# Domino_I2S_No_Teardrop.net
KiCad netlist of a schematic drawn in EAGLE
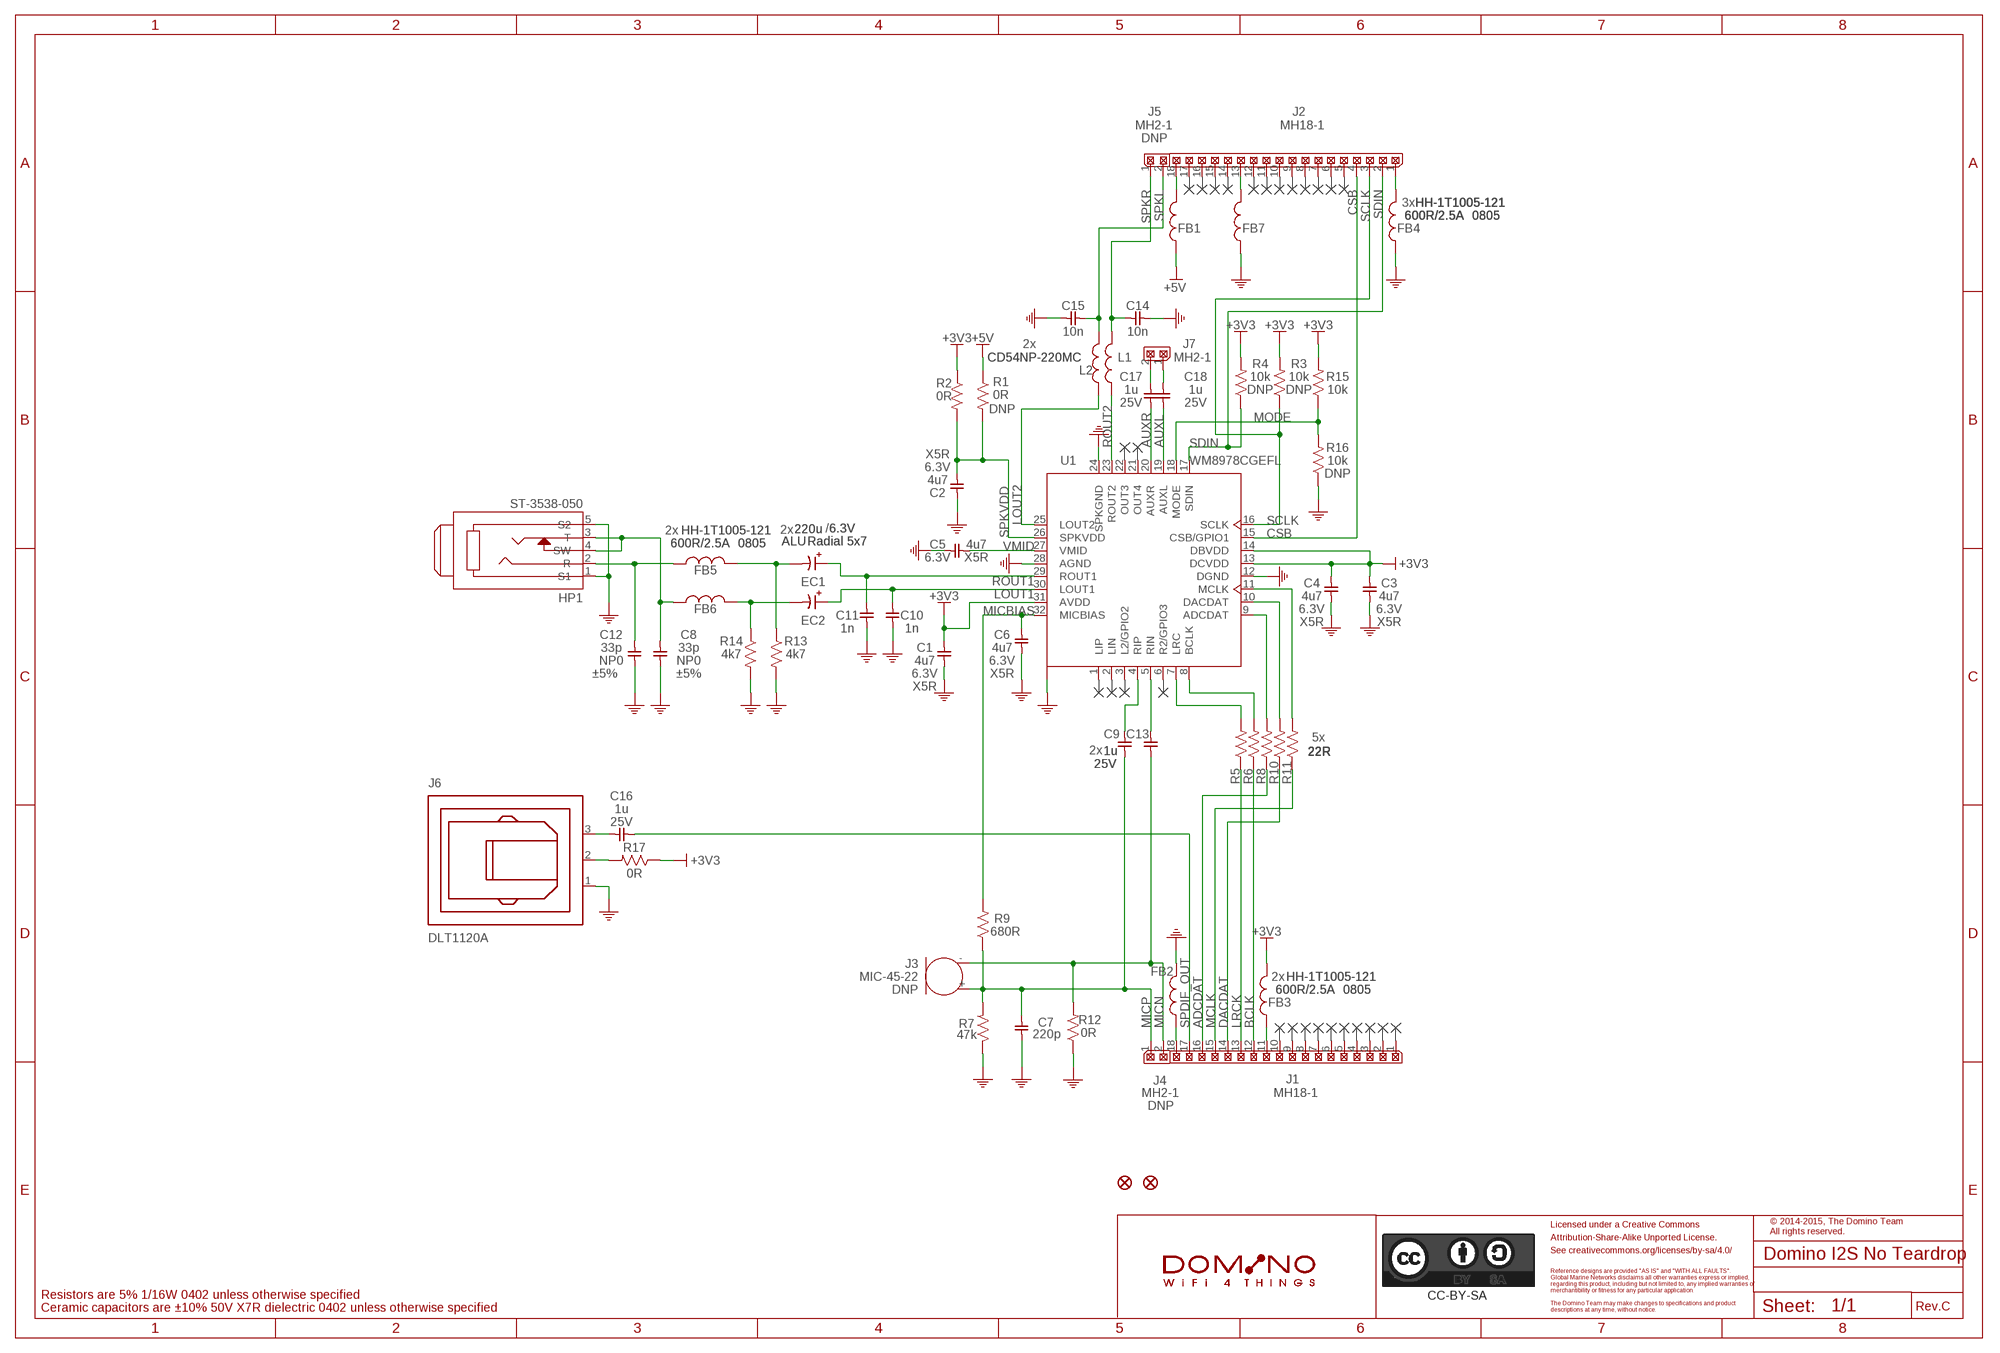
[diagram p0: schematic, sheet 1]

(export (version "E")
  (design (tool "Eeschema 10.0.6"))
  (components
    (comp (ref "C1")
      (value "4u7")
      (footprint "eagle-import:C0402")
      (fields
        (field (name "PARTNO") "C0402_4u7_X5R_10%_CER_6V3")
        (field (name "TC") "X5R")
        (field (name "VOLT") "6.3V")
      )
      (libsource (lib "eagle-import") (part "CAP_0402"))
    )
    (comp (ref "C2")
      (value "4u7")
      (footprint "eagle-import:C0402")
      (fields
        (field (name "PARTNO") "C0402_4u7_X5R_10%_CER_6V3")
        (field (name "TC") "X5R")
        (field (name "VOLT") "6.3V")
      )
      (libsource (lib "eagle-import") (part "CAP_0402"))
    )
    (comp (ref "C3")
      (value "4u7")
      (footprint "eagle-import:C0402")
      (fields
        (field (name "PARTNO") "C0402_4u7_X5R_10%_CER_6V3")
        (field (name "TC") "X5R")
        (field (name "VOLT") "6.3V")
      )
      (libsource (lib "eagle-import") (part "CAP_0402"))
    )
    (comp (ref "C4")
      (value "4u7")
      (footprint "eagle-import:C0402")
      (fields
        (field (name "PARTNO") "C0402_4u7_X5R_10%_CER_6V3")
        (field (name "TC") "X5R")
        (field (name "VOLT") "6.3V")
      )
      (libsource (lib "eagle-import") (part "CAP_0402"))
    )
    (comp (ref "C5")
      (value "4u7")
      (footprint "eagle-import:C0402")
      (fields
        (field (name "PARTNO") "C0402_4u7_X5R_10%_CER_6V3")
        (field (name "TC") "X5R")
        (field (name "VOLT") "6.3V")
      )
      (libsource (lib "eagle-import") (part "CAP_0402"))
    )
    (comp (ref "C6")
      (value "4u7")
      (footprint "eagle-import:C0402")
      (fields
        (field (name "PARTNO") "C0402_4u7_X5R_10%_CER_6V3")
        (field (name "TC") "X5R")
        (field (name "VOLT") "6.3V")
      )
      (libsource (lib "eagle-import") (part "CAP_0402"))
    )
    (comp (ref "C7")
      (value "220p")
      (footprint "eagle-import:C0402")
      (fields (field (name "PARTNO") "C0402_220p_X7R_10%_CER_50V"))
      (libsource (lib "eagle-import") (part "CAP_0402"))
    )
    (comp (ref "C8")
      (value "33p")
      (footprint "eagle-import:C0402")
      (fields
        (field (name "PARTNO") "C0402_33p_NP0_5%_CER_50V")
        (field (name "TC") "NP0")
        (field (name "TOL") "±5%")
      )
      (libsource (lib "eagle-import") (part "CAP_0402"))
    )
    (comp (ref "C9")
      (value "1u")
      (footprint "eagle-import:C0402")
      (fields (field (name "PARTNO") "C0402_1u_X7R_10%_CER_25V") (field (name "VOLT") "25V"))
      (libsource (lib "eagle-import") (part "CAP_0402"))
    )
    (comp (ref "C10")
      (value "1n")
      (footprint "eagle-import:C0402")
      (fields (field (name "PARTNO") "C0402_1n_X7R_10%_CER_50V"))
      (libsource (lib "eagle-import") (part "CAP_0402"))
    )
    (comp (ref "C11")
      (value "1n")
      (footprint "eagle-import:C0402")
      (fields (field (name "PARTNO") "C0402_1n_X7R_10%_CER_50V"))
      (libsource (lib "eagle-import") (part "CAP_0402"))
    )
    (comp (ref "C12")
      (value "33p")
      (footprint "eagle-import:C0402")
      (fields
        (field (name "PARTNO") "C0402_33p_NP0_5%_CER_50V")
        (field (name "TC") "NP0")
        (field (name "TOL") "±5%")
      )
      (libsource (lib "eagle-import") (part "CAP_0402"))
    )
    (comp (ref "C13")
      (value "1u")
      (footprint "eagle-import:C0402")
      (fields (field (name "PARTNO") "C0402_1u_X7R_10%_CER_25V") (field (name "VOLT") "25V"))
      (libsource (lib "eagle-import") (part "CAP_0402"))
    )
    (comp (ref "C14")
      (value "10n")
      (footprint "eagle-import:C0402")
      (fields (field (name "PARTNO") "C0402_10n_X7R_10%_CER_50V"))
      (libsource (lib "eagle-import") (part "CAP_0402"))
    )
    (comp (ref "C15")
      (value "10n")
      (footprint "eagle-import:C0402")
      (fields (field (name "PARTNO") "C0402_10n_X7R_10%_CER_50V"))
      (libsource (lib "eagle-import") (part "CAP_0402"))
    )
    (comp (ref "C16")
      (value "1u")
      (footprint "eagle-import:C0402")
      (fields (field (name "PARTNO") "C0402_1u_X7R_10%_CER_25V") (field (name "VOLT") "25V"))
      (libsource (lib "eagle-import") (part "CAP_0402"))
    )
    (comp (ref "C17")
      (value "1u")
      (footprint "eagle-import:C0402")
      (fields (field (name "PARTNO") "C0402_1u_X7R_10%_CER_25V") (field (name "VOLT") "25V"))
      (libsource (lib "eagle-import") (part "CAP_0402"))
    )
    (comp (ref "C18")
      (value "1u")
      (footprint "eagle-import:C0402")
      (fields (field (name "PARTNO") "C0402_1u_X7R_10%_CER_25V") (field (name "VOLT") "25V"))
      (libsource (lib "eagle-import") (part "CAP_0402"))
    )
    (comp (ref "CC-BY-SA101")
      (value "CC-BY-SA_LOGO")
      (footprint "eagle-import:CC-BY-SA_LOGO")
      (libsource (lib "eagle-import") (part "CC-BY-SA_LOGO"))
    )
    (comp (ref "EC1")
      (value "220u")
      (footprint "eagle-import:E2-5")
      (fields
        (field (name "SIZE") "Radial 5x7")
        (field (name "TYPE") "ALU")
        (field (name "PARTNO") "C2-5x7_220u_ALU_20%_RAD_6V3")
        (field (name "VOLT") "6.3V")
      )
      (libsource (lib "eagle-import") (part "CPOL_?E2-5X7"))
    )
    (comp (ref "EC2")
      (value "220u")
      (footprint "eagle-import:E2-5")
      (fields
        (field (name "SIZE") "Radial 5x7")
        (field (name "TYPE") "ALU")
        (field (name "PARTNO") "C2-5x7_220u_ALU_20%_RAD_6V3")
        (field (name "VOLT") "6.3V")
      )
      (libsource (lib "eagle-import") (part "CPOL_?E2-5X7"))
    )
    (comp (ref "F1")
      (value "FIDUCIAL")
      (footprint "eagle-import:FIDUCIAL")
      (libsource (lib "eagle-import") (part "FIDUCIAL"))
    )
    (comp (ref "F2")
      (value "FIDUCIAL")
      (footprint "eagle-import:FIDUCIAL")
      (libsource (lib "eagle-import") (part "FIDUCIAL"))
    )
    (comp (ref "FB1")
      (value "HH-1T1005-121")
      (footprint "eagle-import:FB0805")
      (fields
        (field (name "SIZE") "0805")
        (field (name "OPT") "600R/2.5A")
        (field (name "PARTNO") "HH-1T2012-601")
      )
      (libsource (lib "eagle-import") (part "FB_0805"))
    )
    (comp (ref "FB2")
      (value "HH-1T1005-121")
      (footprint "eagle-import:FB0805")
      (fields
        (field (name "SIZE") "0805")
        (field (name "OPT") "600R/2.5A")
        (field (name "PARTNO") "HH-1T2012-601")
      )
      (libsource (lib "eagle-import") (part "FB_0805"))
    )
    (comp (ref "FB3")
      (value "HH-1T1005-121")
      (footprint "eagle-import:FB0805")
      (fields
        (field (name "SIZE") "0805")
        (field (name "OPT") "600R/2.5A")
        (field (name "PARTNO") "HH-1T2012-601")
      )
      (libsource (lib "eagle-import") (part "FB_0805"))
    )
    (comp (ref "FB4")
      (value "HH-1T1005-121")
      (footprint "eagle-import:FB0805")
      (fields
        (field (name "SIZE") "0805")
        (field (name "OPT") "600R/2.5A")
        (field (name "PARTNO") "HH-1T2012-601")
      )
      (libsource (lib "eagle-import") (part "FB_0805"))
    )
    (comp (ref "FB5")
      (value "HH-1T1005-121")
      (footprint "eagle-import:FB0805")
      (fields
        (field (name "SIZE") "0805")
        (field (name "OPT") "600R/2.5A")
        (field (name "PARTNO") "HH-1T2012-601")
      )
      (libsource (lib "eagle-import") (part "FB_0805"))
    )
    (comp (ref "FB6")
      (value "HH-1T1005-121")
      (footprint "eagle-import:FB0805")
      (fields
        (field (name "SIZE") "0805")
        (field (name "OPT") "600R/2.5A")
        (field (name "PARTNO") "HH-1T2012-601")
      )
      (libsource (lib "eagle-import") (part "FB_0805"))
    )
    (comp (ref "FB7")
      (value "HH-1T1005-121")
      (footprint "eagle-import:FB0805")
      (fields
        (field (name "SIZE") "0805")
        (field (name "OPT") "600R/2.5A")
        (field (name "PARTNO") "HH-1T2012-601")
      )
      (libsource (lib "eagle-import") (part "FB_0805"))
    )
    (comp (ref "HP1")
      (value "ST-3538-050")
      (footprint "eagle-import:ST-3538-050")
      (libsource (lib "eagle-import") (part "ST-3538-050"))
    )
    (comp (ref "J1")
      (value "MH18-1")
      (footprint "eagle-import:MH18-1-0.1")
      (fields (field (name "PARTNO") "MH18-1-0.1"))
      (libsource (lib "eagle-import") (part "MH18-1"))
    )
    (comp (ref "J2")
      (value "MH18-1")
      (footprint "eagle-import:MH18-1-0.1")
      (fields (field (name "PARTNO") "MH18-1-0.1"))
      (libsource (lib "eagle-import") (part "MH18-1"))
    )
    (comp (ref "J3")
      (value "MIC-45-22")
      (footprint "eagle-import:MIC-45-22")
      (libsource (lib "eagle-import") (part "MIC-45-22"))
    )
    (comp (ref "J4")
      (value "MH2-1")
      (footprint "eagle-import:MH2-1-0.1")
      (fields (field (name "PARTNO") "MH2-1-0.1"))
      (libsource (lib "eagle-import") (part "MH2-1"))
    )
    (comp (ref "J5")
      (value "MH2-1")
      (footprint "eagle-import:MH2-1-0.1")
      (fields (field (name "PARTNO") "MH2-1-0.1"))
      (libsource (lib "eagle-import") (part "MH2-1"))
    )
    (comp (ref "J6")
      (value "DLT1120A")
      (footprint "eagle-import:DLT1120A")
      (libsource (lib "eagle-import") (part "DLT1120A"))
    )
    (comp (ref "J7")
      (value "MH2-1")
      (footprint "eagle-import:MH2-1-0.1")
      (fields (field (name "PARTNO") "MH2-1-0.1"))
      (libsource (lib "eagle-import") (part "MH2-1"))
    )
    (comp (ref "L1")
      (value "CD54NP-220MC")
      (footprint "eagle-import:CD54")
      (libsource (lib "eagle-import") (part "CD54NP-MC220"))
    )
    (comp (ref "L2")
      (value "CD54NP-220MC")
      (footprint "eagle-import:CD54")
      (libsource (lib "eagle-import") (part "CD54NP-MC220"))
    )
    (comp (ref "R1")
      (value "0R")
      (footprint "eagle-import:R0402")
      (fields (field (name "PARTNO") "R0402_0R_5%_62.5mW"))
      (libsource (lib "eagle-import") (part "RES_0402"))
    )
    (comp (ref "R2")
      (value "0R")
      (footprint "eagle-import:R0402")
      (fields (field (name "PARTNO") "R0402_0R_5%_62.5mW"))
      (libsource (lib "eagle-import") (part "RES_0402"))
    )
    (comp (ref "R3")
      (value "10k")
      (footprint "eagle-import:R0402")
      (fields (field (name "PARTNO") "R0402_10k_5%_62.5mW"))
      (libsource (lib "eagle-import") (part "RES_0402"))
    )
    (comp (ref "R4")
      (value "10k")
      (footprint "eagle-import:R0402")
      (fields (field (name "PARTNO") "R0402_10k_5%_62.5mW"))
      (libsource (lib "eagle-import") (part "RES_0402"))
    )
    (comp (ref "R5")
      (value "22R")
      (footprint "eagle-import:R0402")
      (fields (field (name "PARTNO") "R0402_22R_5%_62.5mW"))
      (libsource (lib "eagle-import") (part "RES_0402"))
    )
    (comp (ref "R6")
      (value "22R")
      (footprint "eagle-import:R0402")
      (fields (field (name "PARTNO") "R0402_22R_5%_62.5mW"))
      (libsource (lib "eagle-import") (part "RES_0402"))
    )
    (comp (ref "R7")
      (value "47k")
      (footprint "eagle-import:R0402")
      (fields (field (name "PARTNO") "R0402_47k_5%_62.5mW"))
      (libsource (lib "eagle-import") (part "RES_0402"))
    )
    (comp (ref "R8")
      (value "22R")
      (footprint "eagle-import:R0402")
      (fields (field (name "PARTNO") "R0402_22R_5%_62.5mW"))
      (libsource (lib "eagle-import") (part "RES_0402"))
    )
    (comp (ref "R9")
      (value "680R")
      (footprint "eagle-import:R0402")
      (fields (field (name "PARTNO") "R0402_680R_5%_62.5mW"))
      (libsource (lib "eagle-import") (part "RES_0402"))
    )
    (comp (ref "R10")
      (value "22R")
      (footprint "eagle-import:R0402")
      (fields (field (name "PARTNO") "R0402_22R_5%_62.5mW"))
      (libsource (lib "eagle-import") (part "RES_0402"))
    )
    (comp (ref "R11")
      (value "22R")
      (footprint "eagle-import:R0402")
      (fields (field (name "PARTNO") "R0402_22R_5%_62.5mW"))
      (libsource (lib "eagle-import") (part "RES_0402"))
    )
    (comp (ref "R12")
      (value "0R")
      (footprint "eagle-import:R0402")
      (fields (field (name "PARTNO") "R0402_0R_5%_62.5mW"))
      (libsource (lib "eagle-import") (part "RES_0402"))
    )
    (comp (ref "R13")
      (value "4k7")
      (footprint "eagle-import:R0402")
      (fields (field (name "PARTNO") "R0402_4k7_5%_62.5mW"))
      (libsource (lib "eagle-import") (part "RES_0402"))
    )
    (comp (ref "R14")
      (value "4k7")
      (footprint "eagle-import:R0402")
      (fields (field (name "PARTNO") "R0402_4k7_5%_62.5mW"))
      (libsource (lib "eagle-import") (part "RES_0402"))
    )
    (comp (ref "R15")
      (value "10k")
      (footprint "eagle-import:R0402")
      (fields (field (name "PARTNO") "R0402_10k_5%_62.5mW"))
      (libsource (lib "eagle-import") (part "RES_0402"))
    )
    (comp (ref "R16")
      (value "10k")
      (footprint "eagle-import:R0402")
      (fields (field (name "PARTNO") "R0402_10k_5%_62.5mW"))
      (libsource (lib "eagle-import") (part "RES_0402"))
    )
    (comp (ref "R17")
      (value "0R")
      (footprint "eagle-import:R0402")
      (fields (field (name "PARTNO") "R0402_0R_5%_62.5mW"))
      (libsource (lib "eagle-import") (part "RES_0402"))
    )
    (comp (ref "S101")
      (value "DOMINO_LOGO")
      (footprint "eagle-import:DOMINO_LOGO")
      (libsource (lib "eagle-import") (part "DOMINO_LOGO"))
    )
    (comp (ref "U1")
      (value "WM8978CGEFL")
      (footprint "eagle-import:QFN-32_EP_5X5")
      (libsource (lib "eagle-import") (part "WM8978CGEFL"))
    )
  )
  (nets
    (net (code "1") (name "+3V3") (class "Default")
      (node (ref "C1") (pin "1") (pinfunction "1_1") (pintype "passive"))
      (node (ref "C3") (pin "1") (pinfunction "1_1") (pintype "passive"))
      (node (ref "C4") (pin "1") (pinfunction "1_1") (pintype "passive"))
      (node (ref "FB3") (pin "2") (pinfunction "2_2") (pintype "passive"))
      (node (ref "R15") (pin "2") (pinfunction "2_2") (pintype "passive"))
      (node (ref "R17") (pin "1") (pinfunction "1_1") (pintype "passive"))
      (node (ref "R2") (pin "1") (pinfunction "1_1") (pintype "passive"))
      (node (ref "R3") (pin "2") (pinfunction "2_2") (pintype "passive"))
      (node (ref "R4") (pin "2") (pinfunction "2_2") (pintype "passive"))
      (node (ref "U1") (pin "13") (pinfunction "DCVDD_13") (pintype "power_in"))
      (node (ref "U1") (pin "14") (pinfunction "DBVDD_14") (pintype "power_in"))
      (node (ref "U1") (pin "31") (pinfunction "AVDD_31") (pintype "power_in"))
    )
    (net (code "2") (name "+5V") (class "Default")
      (node (ref "FB1") (pin "1") (pinfunction "1_1") (pintype "passive"))
      (node (ref "R1") (pin "1") (pinfunction "1_1") (pintype "passive"))
    )
    (net (code "3") (name "/ADCDAT") (class "Default")
      (node (ref "J1") (pin "16") (pinfunction "16_16") (pintype "passive"))
      (node (ref "R8") (pin "1") (pinfunction "1_1") (pintype "passive"))
    )
    (net (code "4") (name "/AUXL") (class "Default")
      (node (ref "C18") (pin "2") (pinfunction "2_2") (pintype "passive"))
      (node (ref "U1") (pin "19") (pinfunction "AUXL_19") (pintype "passive"))
    )
    (net (code "5") (name "/AUXR") (class "Default")
      (node (ref "C17") (pin "2") (pinfunction "2_2") (pintype "passive"))
      (node (ref "U1") (pin "20") (pinfunction "AUXR_20") (pintype "passive"))
    )
    (net (code "6") (name "/BCLK") (class "Default")
      (node (ref "J1") (pin "12") (pinfunction "12_12") (pintype "passive"))
      (node (ref "R6") (pin "1") (pinfunction "1_1") (pintype "passive"))
    )
    (net (code "7") (name "/CSB") (class "Default")
      (node (ref "J2") (pin "4") (pinfunction "4_4") (pintype "passive"))
      (node (ref "U1") (pin "15") (pinfunction "CSB/GPIO1_15") (pintype "bidirectional"))
    )
    (net (code "8") (name "/DACDAT") (class "Default")
      (node (ref "J1") (pin "14") (pinfunction "14_14") (pintype "passive"))
      (node (ref "R10") (pin "1") (pinfunction "1_1") (pintype "passive"))
    )
    (net (code "9") (name "/LOUT1") (class "Default")
      (node (ref "C10") (pin "1") (pinfunction "1_1") (pintype "passive"))
      (node (ref "EC2") (pin "1") (pinfunction "+_1") (pintype "passive"))
      (node (ref "U1") (pin "30") (pinfunction "LOUT1_30") (pintype "passive"))
    )
    (net (code "10") (name "/LOUT2") (class "Default")
      (node (ref "L2") (pin "1") (pinfunction "1_1") (pintype "passive"))
      (node (ref "U1") (pin "25") (pinfunction "LOUT2_25") (pintype "passive"))
    )
    (net (code "11") (name "/LRCK") (class "Default")
      (node (ref "J1") (pin "13") (pinfunction "13_13") (pintype "passive"))
      (node (ref "R5") (pin "1") (pinfunction "1_1") (pintype "passive"))
    )
    (net (code "12") (name "/MCLK") (class "Default")
      (node (ref "J1") (pin "15") (pinfunction "15_15") (pintype "passive"))
      (node (ref "R11") (pin "1") (pinfunction "1_1") (pintype "passive"))
    )
    (net (code "13") (name "/MICBIAS") (class "Default")
      (node (ref "C6") (pin "1") (pinfunction "1_1") (pintype "passive"))
      (node (ref "R9") (pin "2") (pinfunction "2_2") (pintype "passive"))
      (node (ref "U1") (pin "32") (pinfunction "MICBIAS_32") (pintype "passive"))
    )
    (net (code "14") (name "/MICN") (class "Default")
      (node (ref "C13") (pin "2") (pinfunction "2_2") (pintype "passive"))
      (node (ref "J3") (pin "-") (pinfunction "-_-") (pintype "passive"))
      (node (ref "J4") (pin "2") (pinfunction "2_2") (pintype "passive"))
      (node (ref "R12") (pin "2") (pinfunction "2_2") (pintype "passive"))
    )
    (net (code "15") (name "/MICP") (class "Default")
      (node (ref "C7") (pin "1") (pinfunction "1_1") (pintype "passive"))
      (node (ref "C9") (pin "2") (pinfunction "2_2") (pintype "passive"))
      (node (ref "J3") (pin "+") (pinfunction "+_+") (pintype "passive"))
      (node (ref "J4") (pin "1") (pinfunction "1_1") (pintype "passive"))
      (node (ref "R7") (pin "2") (pinfunction "2_2") (pintype "passive"))
      (node (ref "R9") (pin "1") (pinfunction "1_1") (pintype "passive"))
    )
    (net (code "16") (name "/MODE") (class "Default")
      (node (ref "R15") (pin "1") (pinfunction "1_1") (pintype "passive"))
      (node (ref "R16") (pin "2") (pinfunction "2_2") (pintype "passive"))
      (node (ref "U1") (pin "18") (pinfunction "MODE_18") (pintype "input"))
    )
    (net (code "17") (name "/ROUT1") (class "Default")
      (node (ref "C11") (pin "1") (pinfunction "1_1") (pintype "passive"))
      (node (ref "EC1") (pin "1") (pinfunction "+_1") (pintype "passive"))
      (node (ref "U1") (pin "29") (pinfunction "ROUT1_29") (pintype "passive"))
    )
    (net (code "18") (name "/ROUT2") (class "Default")
      (node (ref "L1") (pin "1") (pinfunction "1_1") (pintype "passive"))
      (node (ref "U1") (pin "23") (pinfunction "ROUT2_23") (pintype "passive"))
    )
    (net (code "19") (name "/SCLK") (class "Default")
      (node (ref "J2") (pin "3") (pinfunction "3_3") (pintype "passive"))
      (node (ref "R3") (pin "1") (pinfunction "1_1") (pintype "passive"))
      (node (ref "U1") (pin "16") (pinfunction "SCLK_16") (pintype "input"))
    )
    (net (code "20") (name "/SDIN") (class "Default")
      (node (ref "J2") (pin "2") (pinfunction "2_2") (pintype "passive"))
      (node (ref "R4") (pin "1") (pinfunction "1_1") (pintype "passive"))
      (node (ref "U1") (pin "17") (pinfunction "SDIN_17") (pintype "bidirectional"))
    )
    (net (code "21") (name "/SPDIF_OUT") (class "Default")
      (node (ref "C16") (pin "2") (pinfunction "2_2") (pintype "passive"))
      (node (ref "J1") (pin "17") (pinfunction "17_17") (pintype "passive"))
    )
    (net (code "22") (name "/SPKL") (class "Default")
      (node (ref "C15") (pin "1") (pinfunction "1_1") (pintype "passive"))
      (node (ref "J5") (pin "2") (pinfunction "2_2") (pintype "passive"))
      (node (ref "L2") (pin "2") (pinfunction "2_2") (pintype "passive"))
    )
    (net (code "23") (name "/SPKR") (class "Default")
      (node (ref "C14") (pin "1") (pinfunction "1_1") (pintype "passive"))
      (node (ref "J5") (pin "1") (pinfunction "1_1") (pintype "passive"))
      (node (ref "L1") (pin "2") (pinfunction "2_2") (pintype "passive"))
    )
    (net (code "24") (name "/SPKVDD") (class "Default")
      (node (ref "C2") (pin "2") (pinfunction "2_2") (pintype "passive"))
      (node (ref "R1") (pin "2") (pinfunction "2_2") (pintype "passive"))
      (node (ref "R2") (pin "2") (pinfunction "2_2") (pintype "passive"))
      (node (ref "U1") (pin "26") (pinfunction "SPKVDD_26") (pintype "power_in"))
    )
    (net (code "25") (name "/VMID") (class "Default")
      (node (ref "C5") (pin "2") (pinfunction "2_2") (pintype "passive"))
      (node (ref "U1") (pin "27") (pinfunction "VMID_27") (pintype "passive"))
    )
    (net (code "26") (name "GND") (class "Default")
      (node (ref "C1") (pin "2") (pinfunction "2_2") (pintype "passive"))
      (node (ref "C10") (pin "2") (pinfunction "2_2") (pintype "passive"))
      (node (ref "C11") (pin "2") (pinfunction "2_2") (pintype "passive"))
      (node (ref "C12") (pin "1") (pinfunction "1_1") (pintype "passive"))
      (node (ref "C14") (pin "2") (pinfunction "2_2") (pintype "passive"))
      (node (ref "C15") (pin "2") (pinfunction "2_2") (pintype "passive"))
      (node (ref "C2") (pin "1") (pinfunction "1_1") (pintype "passive"))
      (node (ref "C3") (pin "2") (pinfunction "2_2") (pintype "passive"))
      (node (ref "C4") (pin "2") (pinfunction "2_2") (pintype "passive"))
      (node (ref "C5") (pin "1") (pinfunction "1_1") (pintype "passive"))
      (node (ref "C6") (pin "2") (pinfunction "2_2") (pintype "passive"))
      (node (ref "C7") (pin "2") (pinfunction "2_2") (pintype "passive"))
      (node (ref "C8") (pin "1") (pinfunction "1_1") (pintype "passive"))
      (node (ref "FB2") (pin "2") (pinfunction "2_2") (pintype "passive"))
      (node (ref "FB4") (pin "1") (pinfunction "1_1") (pintype "passive"))
      (node (ref "FB7") (pin "1") (pinfunction "1_1") (pintype "passive"))
      (node (ref "HP1") (pin "1") (pinfunction "S1_1") (pintype "passive"))
      (node (ref "HP1") (pin "5") (pinfunction "S2_5") (pintype "passive"))
      (node (ref "J6") (pin "1") (pinfunction "GND_1") (pintype "power_in"))
      (node (ref "R12") (pin "1") (pinfunction "1_1") (pintype "passive"))
      (node (ref "R13") (pin "2") (pinfunction "2_2") (pintype "passive"))
      (node (ref "R14") (pin "2") (pinfunction "2_2") (pintype "passive"))
      (node (ref "R16") (pin "1") (pinfunction "1_1") (pintype "passive"))
      (node (ref "R7") (pin "1") (pinfunction "1_1") (pintype "passive"))
      (node (ref "U1") (pin "12") (pinfunction "DGND_12") (pintype "power_in"))
      (node (ref "U1") (pin "24") (pinfunction "SPKGND_24") (pintype "power_in"))
      (node (ref "U1") (pin "28") (pinfunction "AGND_28") (pintype "power_in"))
      (node (ref "U1") (pin "PAD") (pinfunction "PAD_PAD") (pintype "power_in"))
    )
    (net (code "27") (name "Net-(C17-Pad1)") (class "Default")
      (node (ref "C17") (pin "1") (pinfunction "1_1") (pintype "passive"))
      (node (ref "J7") (pin "2") (pinfunction "2_2") (pintype "passive"))
    )
    (net (code "28") (name "Net-(C18-Pad1)") (class "Default")
      (node (ref "C18") (pin "1") (pinfunction "1_1") (pintype "passive"))
      (node (ref "J7") (pin "1") (pinfunction "1_1") (pintype "passive"))
    )
    (net (code "29") (name "Net-(EC1--)") (class "Default")
      (node (ref "EC1") (pin "2") (pinfunction "-_2") (pintype "passive"))
      (node (ref "FB5") (pin "2") (pinfunction "2_2") (pintype "passive"))
      (node (ref "R13") (pin "1") (pinfunction "1_1") (pintype "passive"))
    )
    (net (code "30") (name "Net-(EC2--)") (class "Default")
      (node (ref "EC2") (pin "2") (pinfunction "-_2") (pintype "passive"))
      (node (ref "FB6") (pin "2") (pinfunction "2_2") (pintype "passive"))
      (node (ref "R14") (pin "1") (pinfunction "1_1") (pintype "passive"))
    )
    (net (code "31") (name "Net-(FB1-Pad2)") (class "Default")
      (node (ref "FB1") (pin "2") (pinfunction "2_2") (pintype "passive"))
      (node (ref "J2") (pin "18") (pinfunction "18_18") (pintype "passive"))
    )
    (net (code "32") (name "Net-(FB2-Pad1)") (class "Default")
      (node (ref "FB2") (pin "1") (pinfunction "1_1") (pintype "passive"))
      (node (ref "J1") (pin "18") (pinfunction "18_18") (pintype "passive"))
    )
    (net (code "33") (name "Net-(FB3-Pad1)") (class "Default")
      (node (ref "FB3") (pin "1") (pinfunction "1_1") (pintype "passive"))
      (node (ref "J1") (pin "11") (pinfunction "11_11") (pintype "passive"))
    )
    (net (code "34") (name "Net-(FB4-Pad2)") (class "Default")
      (node (ref "FB4") (pin "2") (pinfunction "2_2") (pintype "passive"))
      (node (ref "J2") (pin "1") (pinfunction "1_1") (pintype "passive"))
    )
    (net (code "35") (name "Net-(FB7-Pad2)") (class "Default")
      (node (ref "FB7") (pin "2") (pinfunction "2_2") (pintype "passive"))
      (node (ref "J2") (pin "13") (pinfunction "13_13") (pintype "passive"))
    )
    (net (code "36") (name "Net-(HP1-R)") (class "Default")
      (node (ref "C12") (pin "2") (pinfunction "2_2") (pintype "passive"))
      (node (ref "FB5") (pin "1") (pinfunction "1_1") (pintype "passive"))
      (node (ref "HP1") (pin "2") (pinfunction "R_2") (pintype "passive"))
    )
    (net (code "37") (name "Net-(HP1-SW)") (class "Default")
      (node (ref "C8") (pin "2") (pinfunction "2_2") (pintype "passive"))
      (node (ref "FB6") (pin "1") (pinfunction "1_1") (pintype "passive"))
      (node (ref "HP1") (pin "3") (pinfunction "T_3") (pintype "passive"))
      (node (ref "HP1") (pin "4") (pinfunction "SW_4") (pintype "passive"))
    )
    (net (code "38") (name "Net-(J6-VCC)") (class "Default")
      (node (ref "J6") (pin "2") (pinfunction "VCC_2") (pintype "power_in"))
      (node (ref "R17") (pin "2") (pinfunction "2_2") (pintype "passive"))
    )
    (net (code "39") (name "Net-(J6-VIN)") (class "Default")
      (node (ref "C16") (pin "1") (pinfunction "1_1") (pintype "passive"))
      (node (ref "J6") (pin "3") (pinfunction "VIN_3") (pintype "passive"))
    )
    (net (code "40") (name "Net-(U1-ADCDAT)") (class "Default")
      (node (ref "R8") (pin "2") (pinfunction "2_2") (pintype "passive"))
      (node (ref "U1") (pin "9") (pinfunction "ADCDAT_9") (pintype "output"))
    )
    (net (code "41") (name "Net-(U1-BCLK)") (class "Default")
      (node (ref "R6") (pin "2") (pinfunction "2_2") (pintype "passive"))
      (node (ref "U1") (pin "8") (pinfunction "BCLK_8") (pintype "bidirectional"))
    )
    (net (code "42") (name "Net-(U1-DACDAT)") (class "Default")
      (node (ref "R10") (pin "2") (pinfunction "2_2") (pintype "passive"))
      (node (ref "U1") (pin "10") (pinfunction "DACDAT_10") (pintype "input"))
    )
    (net (code "43") (name "Net-(U1-LRC)") (class "Default")
      (node (ref "R5") (pin "2") (pinfunction "2_2") (pintype "passive"))
      (node (ref "U1") (pin "7") (pinfunction "LRC_7") (pintype "bidirectional"))
    )
    (net (code "44") (name "Net-(U1-MCLK)") (class "Default")
      (node (ref "R11") (pin "2") (pinfunction "2_2") (pintype "passive"))
      (node (ref "U1") (pin "11") (pinfunction "MCLK_11") (pintype "input"))
    )
    (net (code "45") (name "Net-(U1-RIN)") (class "Default")
      (node (ref "C13") (pin "1") (pinfunction "1_1") (pintype "passive"))
      (node (ref "U1") (pin "5") (pinfunction "RIN_5") (pintype "passive"))
    )
    (net (code "46") (name "Net-(U1-RIP)") (class "Default")
      (node (ref "C9") (pin "1") (pinfunction "1_1") (pintype "passive"))
      (node (ref "U1") (pin "4") (pinfunction "RIP_4") (pintype "passive"))
    )
    (net (code "47") (name "unconnected-(J1-Pad1)") (class "Default")
      (node (ref "J1") (pin "1") (pinfunction "1_1") (pintype "passive"))
    )
    (net (code "48") (name "unconnected-(J1-Pad2)") (class "Default")
      (node (ref "J1") (pin "2") (pinfunction "2_2") (pintype "passive"))
    )
    (net (code "49") (name "unconnected-(J1-Pad3)") (class "Default")
      (node (ref "J1") (pin "3") (pinfunction "3_3") (pintype "passive"))
    )
    (net (code "50") (name "unconnected-(J1-Pad4)") (class "Default")
      (node (ref "J1") (pin "4") (pinfunction "4_4") (pintype "passive"))
    )
    (net (code "51") (name "unconnected-(J1-Pad5)") (class "Default")
      (node (ref "J1") (pin "5") (pinfunction "5_5") (pintype "passive"))
    )
    (net (code "52") (name "unconnected-(J1-Pad6)") (class "Default")
      (node (ref "J1") (pin "6") (pinfunction "6_6") (pintype "passive"))
    )
    (net (code "53") (name "unconnected-(J1-Pad7)") (class "Default")
      (node (ref "J1") (pin "7") (pinfunction "7_7") (pintype "passive"))
    )
    (net (code "54") (name "unconnected-(J1-Pad8)") (class "Default")
      (node (ref "J1") (pin "8") (pinfunction "8_8") (pintype "passive"))
    )
    (net (code "55") (name "unconnected-(J1-Pad9)") (class "Default")
      (node (ref "J1") (pin "9") (pinfunction "9_9") (pintype "passive"))
    )
    (net (code "56") (name "unconnected-(J1-Pad10)") (class "Default")
      (node (ref "J1") (pin "10") (pinfunction "10_10") (pintype "passive"))
    )
    (net (code "57") (name "unconnected-(J2-Pad5)") (class "Default")
      (node (ref "J2") (pin "5") (pinfunction "5_5") (pintype "passive"))
    )
    (net (code "58") (name "unconnected-(J2-Pad6)") (class "Default")
      (node (ref "J2") (pin "6") (pinfunction "6_6") (pintype "passive"))
    )
    (net (code "59") (name "unconnected-(J2-Pad7)") (class "Default")
      (node (ref "J2") (pin "7") (pinfunction "7_7") (pintype "passive"))
    )
    (net (code "60") (name "unconnected-(J2-Pad8)") (class "Default")
      (node (ref "J2") (pin "8") (pinfunction "8_8") (pintype "passive"))
    )
    (net (code "61") (name "unconnected-(J2-Pad9)") (class "Default")
      (node (ref "J2") (pin "9") (pinfunction "9_9") (pintype "passive"))
    )
    (net (code "62") (name "unconnected-(J2-Pad10)") (class "Default")
      (node (ref "J2") (pin "10") (pinfunction "10_10") (pintype "passive"))
    )
    (net (code "63") (name "unconnected-(J2-Pad11)") (class "Default")
      (node (ref "J2") (pin "11") (pinfunction "11_11") (pintype "passive"))
    )
    (net (code "64") (name "unconnected-(J2-Pad12)") (class "Default")
      (node (ref "J2") (pin "12") (pinfunction "12_12") (pintype "passive"))
    )
    (net (code "65") (name "unconnected-(J2-Pad14)") (class "Default")
      (node (ref "J2") (pin "14") (pinfunction "14_14") (pintype "passive"))
    )
    (net (code "66") (name "unconnected-(J2-Pad15)") (class "Default")
      (node (ref "J2") (pin "15") (pinfunction "15_15") (pintype "passive"))
    )
    (net (code "67") (name "unconnected-(J2-Pad16)") (class "Default")
      (node (ref "J2") (pin "16") (pinfunction "16_16") (pintype "passive"))
    )
    (net (code "68") (name "unconnected-(J2-Pad17)") (class "Default")
      (node (ref "J2") (pin "17") (pinfunction "17_17") (pintype "passive"))
    )
    (net (code "69") (name "unconnected-(U1-L2{slash}GPIO2-Pad3)") (class "Default")
      (node (ref "U1") (pin "3") (pinfunction "L2/GPIO2_3") (pintype "passive"))
    )
    (net (code "70") (name "unconnected-(U1-LIN-Pad2)") (class "Default")
      (node (ref "U1") (pin "2") (pinfunction "LIN_2") (pintype "passive"))
    )
    (net (code "71") (name "unconnected-(U1-LIP-Pad1)") (class "Default")
      (node (ref "U1") (pin "1") (pinfunction "LIP_1") (pintype "passive"))
    )
    (net (code "72") (name "unconnected-(U1-OUT3-Pad22)") (class "Default")
      (node (ref "U1") (pin "22") (pinfunction "OUT3_22") (pintype "passive"))
    )
    (net (code "73") (name "unconnected-(U1-OUT4-Pad21)") (class "Default")
      (node (ref "U1") (pin "21") (pinfunction "OUT4_21") (pintype "passive"))
    )
    (net (code "74") (name "unconnected-(U1-R2{slash}GPIO3-Pad6)") (class "Default")
      (node (ref "U1") (pin "6") (pinfunction "R2/GPIO3_6") (pintype "passive"))
    )
  )
)
